# Memory_EEPROM.net
KiCad netlist of a schematic drawn in Altium Designer
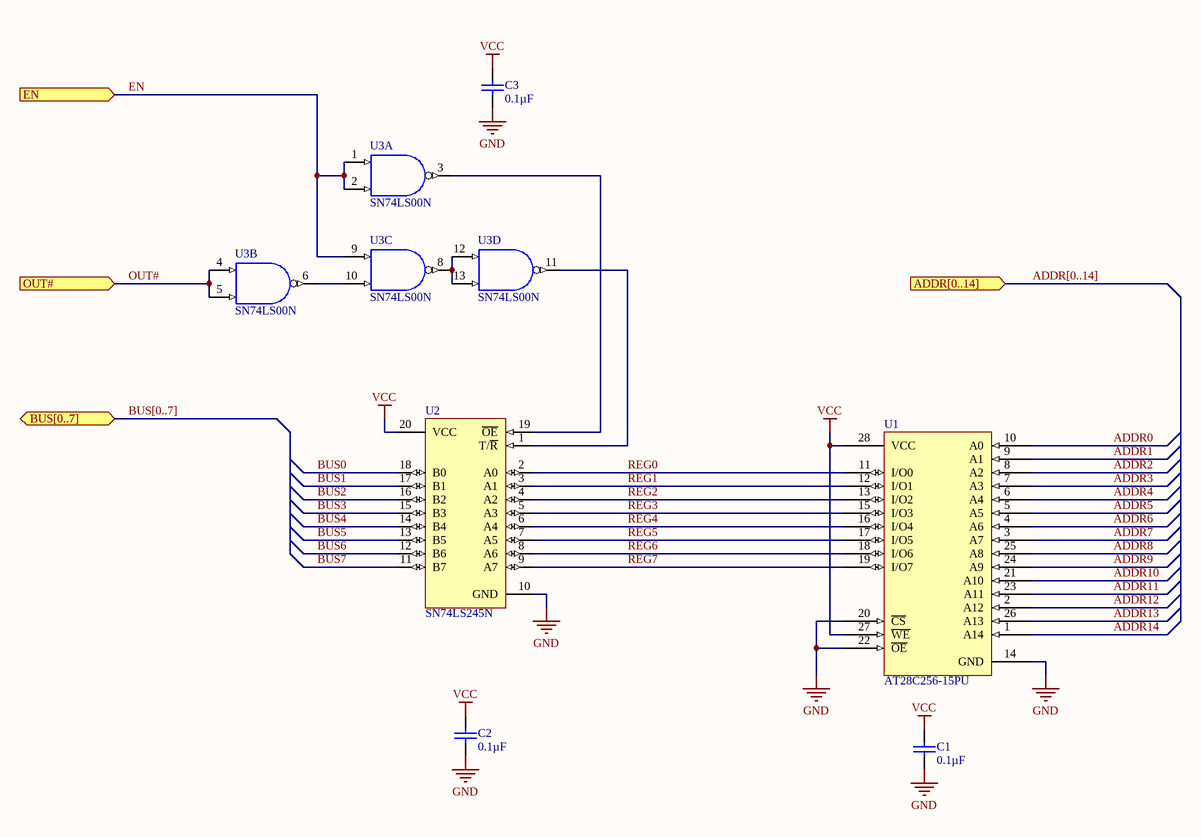
[diagram p0: Memory_EEPROM.SchDoc]

(export (version "E")
  (design (tool "Eeschema 10.0.6"))
  (components
    (comp (ref "C1")
      (value "K104K15X7RF5TL2")
      (footprint "VISH-K104K15X7RF5TL2")
      (description "Ceramic Capacitor, 100 nF, +/- 10%, 50 V, -55 to 125 degC, 2-Pin THD, RoHS, Tape and Reel")
      (fields
        (field (name "MANUFACTURER") "Vishay")
        (field (name "TOLERANCE") "±10%")
        (field (name "CAPACITANCE") "0.1µF")
      )
      (libsource (lib "Altium Content Vault") (part "CAP-NP-2"))
    )
    (comp (ref "C2")
      (value "K104K15X7RF5TL2")
      (footprint "VISH-K104K15X7RF5TL2")
      (description "Ceramic Capacitor, 100 nF, +/- 10%, 50 V, -55 to 125 degC, 2-Pin THD, RoHS, Tape and Reel")
      (fields
        (field (name "MANUFACTURER") "Vishay")
        (field (name "TOLERANCE") "±10%")
        (field (name "CAPACITANCE") "0.1µF")
      )
      (libsource (lib "Altium Content Vault") (part "CAP-NP-2"))
    )
    (comp (ref "C3")
      (value "K104K15X7RF5TL2")
      (footprint "VISH-K104K15X7RF5TL2")
      (description "Ceramic Capacitor, 100 nF, +/- 10%, 50 V, -55 to 125 degC, 2-Pin THD, RoHS, Tape and Reel")
      (fields
        (field (name "MANUFACTURER") "Vishay")
        (field (name "TOLERANCE") "±10%")
        (field (name "CAPACITANCE") "0.1µF")
      )
      (libsource (lib "Altium Content Vault") (part "CAP-NP-2"))
    )
    (comp (ref "U1")
      (value "AT28C256-15PU")
      (footprint "J028")
      (libsource (lib "Schlib1") (part "AT28C256-15PU"))
    )
    (comp (ref "U2")
      (value "SN74LS245N")
      (footprint "N020")
      (description "Octal Bus Transceiver with 3-State Outputs")
      (fields (field (name "PUBLISHER") "Altium Limited"))
      (libsource (lib "TI Interface 8-Bit Line Transceiver") (part "SN74LS245N"))
    )
    (comp (ref "U3")
      (value "SN74LS00N")
      (footprint "N014")
      (description "Quadruple 2-Input Positive-NAND Gate")
      (fields (field (name "PUBLISHER") "Altium Limited"))
      (libsource (lib "TI Logic Gate 2") (part "SN74LS00N"))
    )
  )
  (nets
    (net (code "1") (name "/ADDR0") (class "Default")
      (node (ref "U1") (pin "10") (pinfunction "A0_10") (pintype "input"))
    )
    (net (code "2") (name "/ADDR1") (class "Default")
      (node (ref "U1") (pin "9") (pinfunction "A1_9") (pintype "input"))
    )
    (net (code "3") (name "/ADDR2") (class "Default")
      (node (ref "U1") (pin "8") (pinfunction "A2_8") (pintype "input"))
    )
    (net (code "4") (name "/ADDR3") (class "Default")
      (node (ref "U1") (pin "7") (pinfunction "A3_7") (pintype "input"))
    )
    (net (code "5") (name "/ADDR4") (class "Default")
      (node (ref "U1") (pin "6") (pinfunction "A4_6") (pintype "input"))
    )
    (net (code "6") (name "/ADDR5") (class "Default")
      (node (ref "U1") (pin "5") (pinfunction "A5_5") (pintype "input"))
    )
    (net (code "7") (name "/ADDR6") (class "Default")
      (node (ref "U1") (pin "4") (pinfunction "A6_4") (pintype "input"))
    )
    (net (code "8") (name "/ADDR7") (class "Default")
      (node (ref "U1") (pin "3") (pinfunction "A7_3") (pintype "input"))
    )
    (net (code "9") (name "/ADDR8") (class "Default")
      (node (ref "U1") (pin "25") (pinfunction "A8_25") (pintype "input"))
    )
    (net (code "10") (name "/ADDR9") (class "Default")
      (node (ref "U1") (pin "24") (pinfunction "A9_24") (pintype "input"))
    )
    (net (code "11") (name "/ADDR10") (class "Default")
      (node (ref "U1") (pin "21") (pinfunction "A10_21") (pintype "input"))
    )
    (net (code "12") (name "/ADDR11") (class "Default")
      (node (ref "U1") (pin "23") (pinfunction "A11_23") (pintype "input"))
    )
    (net (code "13") (name "/ADDR12") (class "Default")
      (node (ref "U1") (pin "2") (pinfunction "A12_2") (pintype "input"))
    )
    (net (code "14") (name "/ADDR13") (class "Default")
      (node (ref "U1") (pin "26") (pinfunction "A13_26") (pintype "input"))
    )
    (net (code "15") (name "/ADDR14") (class "Default")
      (node (ref "U1") (pin "1") (pinfunction "A14_1") (pintype "input"))
    )
    (net (code "17") (name "/BUS0") (class "Default")
      (node (ref "U2") (pin "18") (pinfunction "B0_18") (pintype "bidirectional"))
    )
    (net (code "18") (name "/BUS1") (class "Default")
      (node (ref "U2") (pin "17") (pinfunction "B1_17") (pintype "bidirectional"))
    )
    (net (code "19") (name "/BUS2") (class "Default")
      (node (ref "U2") (pin "16") (pinfunction "B2_16") (pintype "bidirectional"))
    )
    (net (code "20") (name "/BUS3") (class "Default")
      (node (ref "U2") (pin "15") (pinfunction "B3_15") (pintype "bidirectional"))
    )
    (net (code "21") (name "/BUS4") (class "Default")
      (node (ref "U2") (pin "14") (pinfunction "B4_14") (pintype "bidirectional"))
    )
    (net (code "22") (name "/BUS5") (class "Default")
      (node (ref "U2") (pin "13") (pinfunction "B5_13") (pintype "bidirectional"))
    )
    (net (code "23") (name "/BUS6") (class "Default")
      (node (ref "U2") (pin "12") (pinfunction "B6_12") (pintype "bidirectional"))
    )
    (net (code "24") (name "/BUS7") (class "Default")
      (node (ref "U2") (pin "11") (pinfunction "B7_11") (pintype "bidirectional"))
    )
    (net (code "26") (name "/EN") (class "Default")
      (node (ref "U3") (pin "1") (pinfunction "A_1") (pintype "input"))
      (node (ref "U3") (pin "2") (pinfunction "B_2") (pintype "input"))
      (node (ref "U3") (pin "9") (pinfunction "A_9") (pintype "input"))
    )
    (net (code "27") (name "/OUT#") (class "Default")
      (node (ref "U3") (pin "4") (pinfunction "A_4") (pintype "input"))
      (node (ref "U3") (pin "5") (pinfunction "B_5") (pintype "input"))
    )
    (net (code "28") (name "/REG0") (class "Default")
      (node (ref "U1") (pin "11") (pinfunction "I/O0_11") (pintype "bidirectional"))
      (node (ref "U2") (pin "2") (pinfunction "A0_2") (pintype "bidirectional"))
    )
    (net (code "29") (name "/REG1") (class "Default")
      (node (ref "U1") (pin "12") (pinfunction "I/O1_12") (pintype "bidirectional"))
      (node (ref "U2") (pin "3") (pinfunction "A1_3") (pintype "bidirectional"))
    )
    (net (code "30") (name "/REG2") (class "Default")
      (node (ref "U1") (pin "13") (pinfunction "I/O2_13") (pintype "bidirectional"))
      (node (ref "U2") (pin "4") (pinfunction "A2_4") (pintype "bidirectional"))
    )
    (net (code "31") (name "/REG3") (class "Default")
      (node (ref "U1") (pin "15") (pinfunction "I/O3_15") (pintype "bidirectional"))
      (node (ref "U2") (pin "5") (pinfunction "A3_5") (pintype "bidirectional"))
    )
    (net (code "32") (name "/REG4") (class "Default")
      (node (ref "U1") (pin "16") (pinfunction "I/O4_16") (pintype "bidirectional"))
      (node (ref "U2") (pin "6") (pinfunction "A4_6") (pintype "bidirectional"))
    )
    (net (code "33") (name "/REG5") (class "Default")
      (node (ref "U1") (pin "17") (pinfunction "I/O5_17") (pintype "bidirectional"))
      (node (ref "U2") (pin "7") (pinfunction "A5_7") (pintype "bidirectional"))
    )
    (net (code "34") (name "/REG6") (class "Default")
      (node (ref "U1") (pin "18") (pinfunction "I/O6_18") (pintype "bidirectional"))
      (node (ref "U2") (pin "8") (pinfunction "A6_8") (pintype "bidirectional"))
    )
    (net (code "35") (name "/REG7") (class "Default")
      (node (ref "U1") (pin "19") (pinfunction "I/O7_19") (pintype "bidirectional"))
      (node (ref "U2") (pin "9") (pinfunction "A7_9") (pintype "bidirectional"))
    )
    (net (code "36") (name "GND") (class "Default")
      (node (ref "C1") (pin "2") (pinfunction "2_2") (pintype "passive"))
      (node (ref "C2") (pin "2") (pinfunction "2_2") (pintype "passive"))
      (node (ref "C3") (pin "2") (pinfunction "2_2") (pintype "passive"))
      (node (ref "U1") (pin "14") (pinfunction "GND_14") (pintype "power_in"))
      (node (ref "U1") (pin "20") (pinfunction "~{CS}_20") (pintype "input"))
      (node (ref "U1") (pin "22") (pinfunction "~{OE}_22") (pintype "input"))
      (node (ref "U2") (pin "10") (pinfunction "GND_10") (pintype "power_in"))
      (node (ref "U3") (pin "7") (pinfunction "GND_7") (pintype "power_in"))
    )
    (net (code "37") (name "Net-(U2-T{slash}~{R})") (class "Default")
      (node (ref "U2") (pin "1") (pinfunction "T/~{R}_1") (pintype "input"))
      (node (ref "U3") (pin "11") (pinfunction "Y_11") (pintype "output"))
    )
    (net (code "38") (name "Net-(U2-~{OE})") (class "Default")
      (node (ref "U2") (pin "19") (pinfunction "~{OE}_19") (pintype "input"))
      (node (ref "U3") (pin "3") (pinfunction "Y_3") (pintype "output"))
    )
    (net (code "39") (name "Net-(U3B-Y)") (class "Default")
      (node (ref "U3") (pin "10") (pinfunction "B_10") (pintype "input"))
      (node (ref "U3") (pin "6") (pinfunction "Y_6") (pintype "output"))
    )
    (net (code "40") (name "Net-(U3C-Y)") (class "Default")
      (node (ref "U3") (pin "12") (pinfunction "A_12") (pintype "input"))
      (node (ref "U3") (pin "13") (pinfunction "B_13") (pintype "input"))
      (node (ref "U3") (pin "8") (pinfunction "Y_8") (pintype "output"))
    )
    (net (code "41") (name "VCC") (class "Default")
      (node (ref "C1") (pin "1") (pinfunction "1_1") (pintype "passive"))
      (node (ref "C2") (pin "1") (pinfunction "1_1") (pintype "passive"))
      (node (ref "C3") (pin "1") (pinfunction "1_1") (pintype "passive"))
      (node (ref "U1") (pin "27") (pinfunction "~{WE}_27") (pintype "input"))
      (node (ref "U1") (pin "28") (pinfunction "VCC_28") (pintype "power_in"))
      (node (ref "U2") (pin "20") (pinfunction "VCC_20") (pintype "power_in"))
      (node (ref "U3") (pin "14") (pinfunction "VCC_14") (pintype "power_in"))
    )
  )
)
